# xkid_0_1.net
KiCad netlist of a schematic drawn in EAGLE
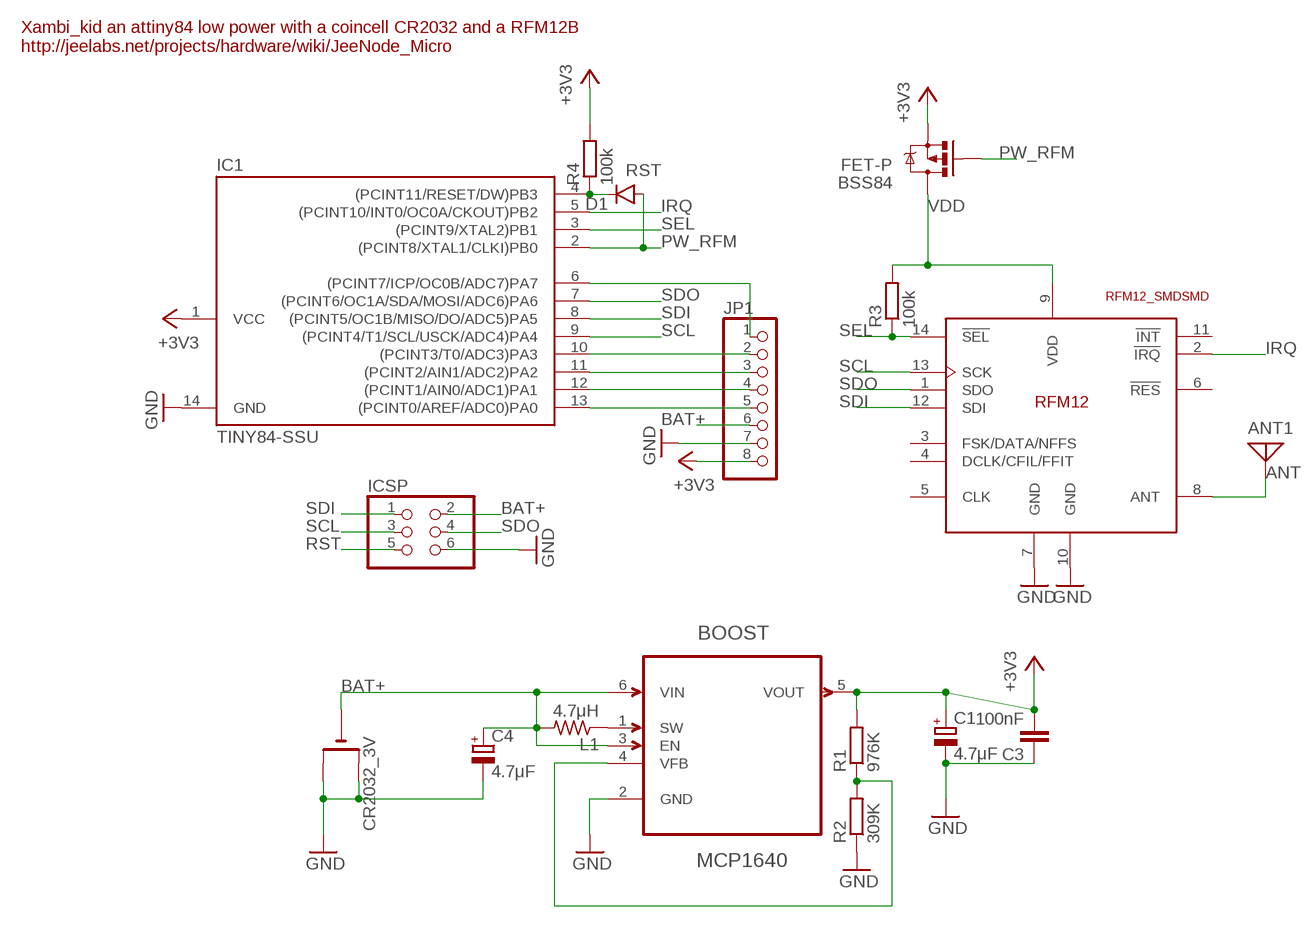
[diagram p0: schematic, sheet 1]

(export (version "E")
  (design (tool "Eeschema 10.0.6"))
  (components
    (comp (ref "ANT1")
      (value "ANTENNA")
      (footprint "eagle-import:PAD-01")
      (libsource (lib "eagle-import") (part "ANTENNA"))
    )
    (comp (ref "BOOST")
      (value "MCP1640")
      (footprint "eagle-import:SOT95P270X145-6N")
      (fields (field (name "MPN") "MCP1640BT-I/CHY"))
      (libsource (lib "eagle-import") (part "MCP1640BT-I/CHY"))
    )
    (comp (ref "BSS84")
      (value "FET-P")
      (footprint "eagle-import:SOT23-3")
      (libsource (lib "eagle-import") (part "MOSFET-PCHANNEL"))
    )
    (comp (ref "C1")
      (value "4.7μF")
      (footprint "eagle-import:CT3216")
      (libsource (lib "eagle-import") (part "CPOL-EUCT3216"))
    )
    (comp (ref "C3")
      (value "100nF")
      (footprint "eagle-import:C0805K")
      (libsource (lib "eagle-import") (part "C-EUC0805K"))
    )
    (comp (ref "C4")
      (value "4.7μF")
      (footprint "eagle-import:CT3216")
      (libsource (lib "eagle-import") (part "CPOL-EUCT3216"))
    )
    (comp (ref "CR2032_3V")
      (value "CR2032THM")
      (footprint "eagle-import:CR2032-THRU")
      (libsource (lib "eagle-import") (part "CR2032THM"))
    )
    (comp (ref "D1")
      (value "DIODESOD")
      (footprint "eagle-import:SOD-323")
      (libsource (lib "eagle-import") (part "DIODESOD"))
    )
    (comp (ref "IC1")
      (value "TINY84-SSU")
      (footprint "eagle-import:SOIC14")
      (libsource (lib "eagle-import") (part "TINY24/44/84-SSU"))
    )
    (comp (ref "ICSP")
      (value "PINHD-2X3")
      (footprint "eagle-import:2X03")
      (libsource (lib "eagle-import") (part "PINHD-2X3"))
    )
    (comp (ref "JP1")
      (value "PINHD-1X8LOCK")
      (footprint "eagle-import:1X08-LOCK")
      (libsource (lib "eagle-import") (part "PINHD-1X8LOCK"))
    )
    (comp (ref "L1")
      (value "4.7μH")
      (footprint "eagle-import:0204_5")
      (libsource (lib "eagle-import") (part "R-US_0204/5"))
    )
    (comp (ref "R1")
      (value "976K")
      (footprint "eagle-import:R0805")
      (libsource (lib "eagle-import") (part "R-EU_R0805"))
    )
    (comp (ref "R2")
      (value "309K")
      (footprint "eagle-import:R0805")
      (libsource (lib "eagle-import") (part "R-EU_R0805"))
    )
    (comp (ref "R3")
      (value "100k")
      (footprint "eagle-import:R0805")
      (libsource (lib "eagle-import") (part "R-EU_R0805"))
    )
    (comp (ref "R4")
      (value "100k")
      (footprint "eagle-import:R0805")
      (libsource (lib "eagle-import") (part "R-EU_R0805"))
    )
    (comp (ref "U$1")
      (value "RFM12_SMDSMD")
      (footprint "eagle-import:RFM12")
      (libsource (lib "eagle-import") (part "RFM12_SMDSMD"))
    )
  )
  (nets
    (net (code "1") (name "+3V3") (class "Default")
      (node (ref "BOOST") (pin "5") (pinfunction "VOUT_5") (pintype "output"))
      (node (ref "BSS84") (pin "2") (pinfunction "S_2") (pintype "passive"))
      (node (ref "C1") (pin "+") (pinfunction "+_+") (pintype "passive"))
      (node (ref "C3") (pin "2") (pinfunction "2_2") (pintype "passive"))
      (node (ref "IC1") (pin "1") (pinfunction "VCC_1") (pintype "power_in"))
      (node (ref "JP1") (pin "8") (pinfunction "8_8") (pintype "passive"))
      (node (ref "R1") (pin "2") (pinfunction "2_2") (pintype "passive"))
      (node (ref "R4") (pin "2") (pinfunction "2_2") (pintype "passive"))
    )
    (net (code "2") (name "/ANT") (class "Default")
      (node (ref "ANT1") (pin "1") (pinfunction "1_1") (pintype "output"))
      (node (ref "U$1") (pin "8") (pinfunction "ANT_8") (pintype "bidirectional"))
    )
    (net (code "3") (name "/BAT+") (class "Default")
      (node (ref "BOOST") (pin "3") (pinfunction "EN_3") (pintype "input"))
      (node (ref "BOOST") (pin "6") (pinfunction "VIN_6") (pintype "input"))
      (node (ref "C4") (pin "+") (pinfunction "+_+") (pintype "passive"))
      (node (ref "CR2032_3V") (pin "-") (pinfunction "-_-") (pintype "passive"))
      (node (ref "ICSP") (pin "2") (pinfunction "2_2") (pintype "passive"))
      (node (ref "JP1") (pin "6") (pinfunction "6_6") (pintype "passive"))
      (node (ref "L1") (pin "2") (pinfunction "2_2") (pintype "passive"))
    )
    (net (code "4") (name "/IRQ") (class "Default")
      (node (ref "IC1") (pin "5") (pinfunction "(PCINT10/INT0/OC0A/CKOUT)PB2_5") (pintype "bidirectional"))
      (node (ref "U$1") (pin "2") (pinfunction "~{IRQ}_2") (pintype "output"))
    )
    (net (code "5") (name "/PW_RFM") (class "Default")
      (node (ref "BSS84") (pin "1") (pinfunction "G_1") (pintype "passive"))
      (node (ref "D1") (pin "A") (pinfunction "A_A") (pintype "passive"))
      (node (ref "IC1") (pin "2") (pinfunction "(PCINT8/XTAL1/CLKI)PB0_2") (pintype "bidirectional"))
    )
    (net (code "6") (name "/RST") (class "Default")
      (node (ref "D1") (pin "C") (pinfunction "C_C") (pintype "passive"))
      (node (ref "IC1") (pin "4") (pinfunction "(PCINT11/RESET/DW)PB3_4") (pintype "bidirectional"))
      (node (ref "ICSP") (pin "5") (pinfunction "5_5") (pintype "passive"))
      (node (ref "R4") (pin "1") (pinfunction "1_1") (pintype "passive"))
    )
    (net (code "7") (name "/SCL") (class "Default")
      (node (ref "IC1") (pin "9") (pinfunction "(PCINT4/T1/SCL/USCK/ADC4)PA4_9") (pintype "bidirectional"))
      (node (ref "ICSP") (pin "3") (pinfunction "3_3") (pintype "passive"))
      (node (ref "U$1") (pin "13") (pinfunction "SCK_13") (pintype "input"))
    )
    (net (code "8") (name "/SDI") (class "Default")
      (node (ref "IC1") (pin "8") (pinfunction "(PCINT5/OC1B/MISO/DO/ADC5)PA5_8") (pintype "bidirectional"))
      (node (ref "ICSP") (pin "1") (pinfunction "1_1") (pintype "passive"))
      (node (ref "U$1") (pin "12") (pinfunction "SDI_12") (pintype "input"))
    )
    (net (code "9") (name "/SDO") (class "Default")
      (node (ref "IC1") (pin "7") (pinfunction "(PCINT6/OC1A/SDA/MOSI/ADC6)PA6_7") (pintype "bidirectional"))
      (node (ref "ICSP") (pin "4") (pinfunction "4_4") (pintype "passive"))
      (node (ref "U$1") (pin "1") (pinfunction "SDO_1") (pintype "output"))
    )
    (net (code "10") (name "/SEL") (class "Default")
      (node (ref "IC1") (pin "3") (pinfunction "(PCINT9/XTAL2)PB1_3") (pintype "bidirectional"))
      (node (ref "R3") (pin "1") (pinfunction "1_1") (pintype "passive"))
      (node (ref "U$1") (pin "14") (pinfunction "~{SEL}_14") (pintype "input"))
    )
    (net (code "11") (name "/VDD") (class "Default")
      (node (ref "BSS84") (pin "3") (pinfunction "D_3") (pintype "passive"))
      (node (ref "R3") (pin "2") (pinfunction "2_2") (pintype "passive"))
      (node (ref "U$1") (pin "9") (pinfunction "VDD_9") (pintype "power_in"))
    )
    (net (code "12") (name "GND") (class "Default")
      (node (ref "BOOST") (pin "2") (pinfunction "GND_2") (pintype "passive"))
      (node (ref "C1") (pin "-") (pinfunction "-_-") (pintype "passive"))
      (node (ref "C3") (pin "1") (pinfunction "1_1") (pintype "passive"))
      (node (ref "C4") (pin "-") (pinfunction "-_-") (pintype "passive"))
      (node (ref "CR2032_3V") (pin "+1") (pinfunction "+_+1") (pintype "passive"))
      (node (ref "CR2032_3V") (pin "+2") (pinfunction "+1_+2") (pintype "passive"))
      (node (ref "IC1") (pin "14") (pinfunction "GND_14") (pintype "power_in"))
      (node (ref "ICSP") (pin "6") (pinfunction "6_6") (pintype "passive"))
      (node (ref "JP1") (pin "7") (pinfunction "7_7") (pintype "passive"))
      (node (ref "R2") (pin "1") (pinfunction "1_1") (pintype "passive"))
      (node (ref "U$1") (pin "10") (pinfunction "GND_10") (pintype "passive"))
      (node (ref "U$1") (pin "7") (pinfunction "GND_7") (pintype "passive"))
    )
    (net (code "13") (name "Net-(BOOST-SW)") (class "Default")
      (node (ref "BOOST") (pin "1") (pinfunction "SW_1") (pintype "input"))
      (node (ref "L1") (pin "1") (pinfunction "1_1") (pintype "passive"))
    )
    (net (code "14") (name "Net-(BOOST-VFB)") (class "Default")
      (node (ref "BOOST") (pin "4") (pinfunction "VFB_4") (pintype "input"))
      (node (ref "R1") (pin "1") (pinfunction "1_1") (pintype "passive"))
      (node (ref "R2") (pin "2") (pinfunction "2_2") (pintype "passive"))
    )
    (net (code "15") (name "Net-(IC1-(PCINT0{slash}AREF{slash}ADC0)PA0)") (class "Default")
      (node (ref "IC1") (pin "13") (pinfunction "(PCINT0/AREF/ADC0)PA0_13") (pintype "bidirectional"))
      (node (ref "JP1") (pin "5") (pinfunction "5_5") (pintype "passive"))
    )
    (net (code "16") (name "Net-(IC1-(PCINT1{slash}AIN0{slash}ADC1)PA1)") (class "Default")
      (node (ref "IC1") (pin "12") (pinfunction "(PCINT1/AIN0/ADC1)PA1_12") (pintype "bidirectional"))
      (node (ref "JP1") (pin "4") (pinfunction "4_4") (pintype "passive"))
    )
    (net (code "17") (name "Net-(IC1-(PCINT2{slash}AIN1{slash}ADC2)PA2)") (class "Default")
      (node (ref "IC1") (pin "11") (pinfunction "(PCINT2/AIN1/ADC2)PA2_11") (pintype "bidirectional"))
      (node (ref "JP1") (pin "3") (pinfunction "3_3") (pintype "passive"))
    )
    (net (code "18") (name "Net-(IC1-(PCINT3{slash}T0{slash}ADC3)PA3)") (class "Default")
      (node (ref "IC1") (pin "10") (pinfunction "(PCINT3/T0/ADC3)PA3_10") (pintype "bidirectional"))
      (node (ref "JP1") (pin "2") (pinfunction "2_2") (pintype "passive"))
    )
    (net (code "19") (name "Net-(IC1-(PCINT7{slash}ICP{slash}OC0B{slash}ADC7)PA7)") (class "Default")
      (node (ref "IC1") (pin "6") (pinfunction "(PCINT7/ICP/OC0B/ADC7)PA7_6") (pintype "bidirectional"))
      (node (ref "JP1") (pin "1") (pinfunction "1_1") (pintype "passive"))
    )
    (net (code "20") (name "unconnected-(U$1-CLK-Pad5)") (class "Default")
      (node (ref "U$1") (pin "5") (pinfunction "CLK_5") (pintype "output"))
    )
    (net (code "21") (name "unconnected-(U$1-DCLK{slash}CFIL{slash}FFIT-Pad4)") (class "Default")
      (node (ref "U$1") (pin "4") (pinfunction "DCLK/CFIL/FFIT_4") (pintype "bidirectional"))
    )
    (net (code "22") (name "unconnected-(U$1-FSK{slash}DATA{slash}NFFS-Pad3)") (class "Default")
      (node (ref "U$1") (pin "3") (pinfunction "FSK/DATA/NFFS_3") (pintype "bidirectional"))
    )
    (net (code "23") (name "unconnected-(U$1-~{INT}-Pad11)") (class "Default")
      (node (ref "U$1") (pin "11") (pinfunction "~{INT}_11") (pintype "bidirectional"))
    )
    (net (code "24") (name "unconnected-(U$1-~{RES}-Pad6)") (class "Default")
      (node (ref "U$1") (pin "6") (pinfunction "~{RES}_6") (pintype "bidirectional"))
    )
  )
)
